# H11R0_Backend.net
KiCad netlist of a schematic drawn in Altium Designer
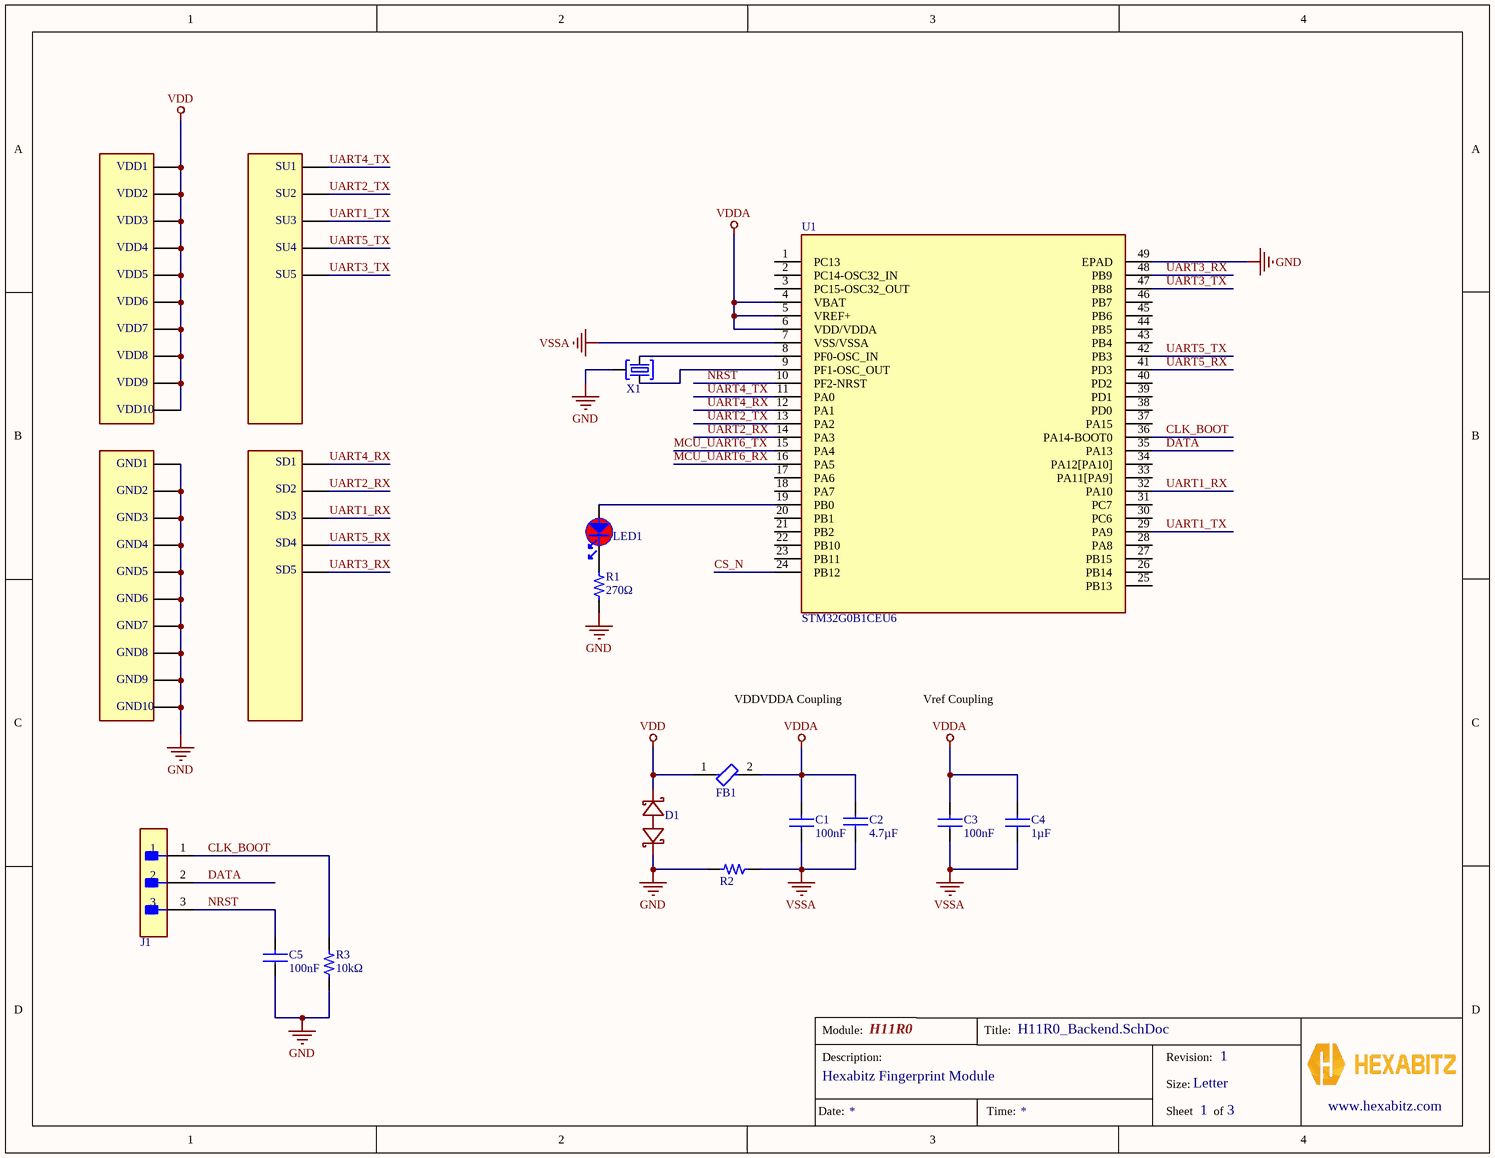
[diagram p0: H11R0_Backend.SchDoc]

(export (version "E")
  (design (tool "Eeschema 10.0.6"))
  (components
    (comp (ref "C1")
      (value "100nF")
      (footprint "C0603")
      (fields
        (field (name "MANUFACTURER") "Samsung Electro-Mechanics")
        (field (name "MANUFACTURER PART NUMBER") "CL10B104KA8NNNC")
        (field (name "TOLERANCE") "10%")
      )
      (libsource (lib "Hexabitz Altium Library") (part "generic Capacitor"))
    )
    (comp (ref "C2")
      (value "4.7µF")
      (footprint "C0805")
      (fields
        (field (name "MANUFACTURER") "Samsung Electro-Mechanics")
        (field (name "MANUFACTURER PART NUMBER") "CL21X475KAQNNNE")
        (field (name "TOLERANCE") "10%")
      )
      (libsource (lib "Hexabitz Altium Library") (part "generic Capacitor"))
    )
    (comp (ref "C3")
      (value "100nF")
      (footprint "C0603")
      (fields
        (field (name "MANUFACTURER") "Samsung Electro-Mechanics")
        (field (name "MANUFACTURER PART NUMBER") "CL10B104KA8NNNC")
        (field (name "TOLERANCE") "10%")
      )
      (libsource (lib "Hexabitz Altium Library") (part "generic Capacitor"))
    )
    (comp (ref "C4")
      (value "1µF")
      (footprint "C0805")
      (description "Ceramic Capacitor, Ceramic, 16V, 10% +Tol, 10% -Tol, X7R, 15% TC, 1uF, Surface Mount, 0805")
      (fields
        (field (name "MANUFACTURER") "Yageo Group")
        (field (name "MANUFACTURER PART NUMBER") "CC0805KKX7R7BB105")
      )
      (libsource (lib "Hexabitz Altium Library") (part "generic Capacitor"))
    )
    (comp (ref "C5")
      (value "100nF")
      (footprint "C0603")
      (fields
        (field (name "MANUFACTURER") "Samsung Electro-Mechanics")
        (field (name "MANUFACTURER PART NUMBER") "CL10B104KA8NNNC")
        (field (name "TOLERANCE") "10%")
      )
      (libsource (lib "Hexabitz Altium Library") (part "generic Capacitor"))
    )
    (comp (ref "D1")
      (value "CDSOD323-T03SC")
      (footprint "SOD2513X114N")
      (description "A 3V, 350W, bi-directional, standard capacitance, SOD323 pkg TVS Diode ¦ Bourns CDSOD323-T03SC")
      (fields (field (name "MANUFACTURER") "Bourns"))
      (libsource (lib "Hexabitz Altium Library") (part "CDSOD323-T03SC"))
    )
    (comp (ref "FB1")
      (value "MMZ1608Y300B")
      (footprint "FP-MMZ1608-0_8-MFG")
      (description "Ferrite Beads 0603 30ohms 1500mA Signal Line AEC-Q200")
      (fields
        (field (name "MANUFACTURER") "TDK")
        (field (name "MANUFACTURER PART NUMBER") "MMZ1608Y300BTD25")
      )
      (libsource (lib "Hexabitz Altium Library") (part "MMZ1608Y300B"))
    )
    (comp (ref "GND1")
      (value "HEXABIT_UART_PORT")
      (footprint "HEXABIT_POWER_PORT_D")
      (libsource (lib "hexabitz_connectors.Library") (part "HEXABIT_POWER_PORT_D"))
    )
    (comp (ref "GND2")
      (value "HEXABIT_UART_PORT")
      (footprint "HEXABIT_POWER_PORT_D")
      (libsource (lib "hexabitz_connectors.Library") (part "HEXABIT_POWER_PORT_D"))
    )
    (comp (ref "GND3")
      (value "HEXABIT_UART_PORT")
      (footprint "HEXABIT_POWER_PORT_D_300R")
      (libsource (lib "hexabitz_connectors.Library") (part "HEXABIT_POWER_PORT_D_300R"))
    )
    (comp (ref "GND4")
      (value "HEXABIT_UART_PORT")
      (footprint "HEXABIT_POWER_PORT_D")
      (libsource (lib "hexabitz_connectors.Library") (part "HEXABIT_POWER_PORT_D"))
    )
    (comp (ref "GND5")
      (value "HEXABIT_UART_PORT")
      (footprint "HEXABIT_POWER_PORT_D")
      (libsource (lib "hexabitz_connectors.Library") (part "HEXABIT_POWER_PORT_D"))
    )
    (comp (ref "GND6")
      (value "HEXABIT_UART_PORT")
      (footprint "HEXABIT_POWER_PORT_D")
      (libsource (lib "hexabitz_connectors.Library") (part "HEXABIT_POWER_PORT_D"))
    )
    (comp (ref "GND7")
      (value "HEXABIT_UART_PORT")
      (footprint "HEXABIT_POWER_PORT_D")
      (libsource (lib "hexabitz_connectors.Library") (part "HEXABIT_POWER_PORT_D"))
    )
    (comp (ref "GND8")
      (value "HEXABIT_UART_PORT")
      (footprint "HEXABIT_POWER_PORT_D_300L")
      (libsource (lib "hexabitz_connectors.Library") (part "HEXABIT_POWER_PORT_D_300L"))
    )
    (comp (ref "GND9")
      (value "HEXABIT_UART_PORT")
      (footprint "HEXABIT_POWER_PORT_D")
      (libsource (lib "hexabitz_connectors.Library") (part "HEXABIT_POWER_PORT_D"))
    )
    (comp (ref "GND10")
      (value "HEXABIT_UART_PORT")
      (footprint "HEXABIT_POWER_PORT_D")
      (libsource (lib "hexabitz_connectors.Library") (part "HEXABIT_POWER_PORT_D"))
    )
    (comp (ref "J1")
      (value "TSW-103-14-G-S")
      (footprint "FP-TSW-103-14-G-S-MFG")
      (description "CONN HEADER VERT 3POS 2.54MM")
      (libsource (lib "Altium Content Vault") (part "cd3439d6ef35ae5d9b27ec4fdd3e828"))
    )
    (comp (ref "LED1")
      (value "VLMS1300-GS08")
      (footprint "FP-6_541-5092_01-4-MFG")
      (description "LED Uni-Color Super Red 639nm 2-Pin Chip 0603(1608Metric) T/R")
      (fields (field (name "MANUFACTURER") "Vishay Semiconductors"))
      (libsource (lib "Hexabitz Altium Library") (part "VLMS1300-GS08"))
    )
    (comp (ref "R1")
      (value "270Ω")
      (footprint "R0603")
      (description "Res Thick Film 0603 270 Ohm 5% 0.1W(1/10W) ±200ppm/C Pad SMD Automotive T/R")
      (fields
        (field (name "MANUFACTURER") "Panasonic")
        (field (name "MANUFACTURER PART NUMBER") "ERJ-3GEYJ271V")
      )
      (libsource (lib "Hexabitz Altium Library") (part "generic Resistor"))
    )
    (comp (ref "R2")
      (value "Manufacturer Part Number")
      (footprint "R0603")
      (libsource (lib "") (part "generic Resistor_1"))
    )
    (comp (ref "R3")
      (value "10kΩ")
      (footprint "R0603")
      (description "100mW Thick Film Resistors ±100ppm/℃ ±1% 10kΩ 0603 Chip Resistor - Surface Mount ROHS")
      (fields
        (field (name "MANUFACTURER") "Yageo Group")
        (field (name "MANUFACTURER PART NUMBER") "RC0603FR-0710KL")
      )
      (libsource (lib "") (part "generic Resistor_2"))
    )
    (comp (ref "SD1")
      (value "HEXABIT_UART_PORT")
      (footprint "HEXABIT_UART_PORT_D")
      (libsource (lib "hexabitz_connectors.Library") (part "HEXABIT_UART_PORT_D"))
    )
    (comp (ref "SD2")
      (value "HEXABIT_UART_PORT")
      (footprint "HEXABIT_UART_PORT_D")
      (libsource (lib "hexabitz_connectors.Library") (part "HEXABIT_UART_PORT_D"))
    )
    (comp (ref "SD3")
      (value "HEXABIT_UART_PORT")
      (footprint "HEXABIT_UART_PORT_D")
      (libsource (lib "hexabitz_connectors.Library") (part "HEXABIT_UART_PORT_D"))
    )
    (comp (ref "SD4")
      (value "HEXABIT_UART_PORT")
      (footprint "HEXABIT_UART_PORT_D")
      (libsource (lib "hexabitz_connectors.Library") (part "HEXABIT_UART_PORT_D"))
    )
    (comp (ref "SD5")
      (value "HEXABIT_UART_PORT")
      (footprint "HEXABIT_UART_PORT_D")
      (libsource (lib "hexabitz_connectors.Library") (part "HEXABIT_UART_PORT_D"))
    )
    (comp (ref "SU1")
      (value "HEXABIT_UART_PORT")
      (footprint "HEXABIT_UART_PORT_U")
      (libsource (lib "hexabitz_connectors.Library") (part "HEXABIT_UART_PORT_U"))
    )
    (comp (ref "SU2")
      (value "HEXABIT_UART_PORT")
      (footprint "HEXABIT_UART_PORT_U")
      (libsource (lib "hexabitz_connectors.Library") (part "HEXABIT_UART_PORT_U"))
    )
    (comp (ref "SU3")
      (value "HEXABIT_UART_PORT")
      (footprint "HEXABIT_UART_PORT_U")
      (libsource (lib "hexabitz_connectors.Library") (part "HEXABIT_UART_PORT_U"))
    )
    (comp (ref "SU4")
      (value "HEXABIT_UART_PORT")
      (footprint "HEXABIT_UART_PORT_U")
      (libsource (lib "hexabitz_connectors.Library") (part "HEXABIT_UART_PORT_U"))
    )
    (comp (ref "SU5")
      (value "HEXABIT_UART_PORT")
      (footprint "HEXABIT_UART_PORT_U")
      (libsource (lib "hexabitz_connectors.Library") (part "HEXABIT_UART_PORT_U"))
    )
    (comp (ref "U1")
      (value "STM32G0B1CEU6")
      (footprint "QFN50P700X700X65-49N-D")
      (description "MCU 32-bit ARM Cortex M0+ RISC 512KB Flash 1.8V/2.5V/3.3V 48-Pin UFQFPN EP Tray")
      (fields
        (field (name "MANUFACTURER") "STMicroelectronics")
        (field (name "MANUFACTURER PART NUMBER") "STM32G0B1CEU6")
      )
      (libsource (lib "Hexabitz Altium Library") (part "STM32G0B1CEU6"))
    )
    (comp (ref "VDD1")
      (value "HEXABIT_UART_PORT")
      (footprint "HEXABIT_POWER_PORT_U")
      (libsource (lib "hexabitz_connectors.Library") (part "HEXABIT_POWER_PORT_U"))
    )
    (comp (ref "VDD2")
      (value "HEXABIT_UART_PORT")
      (footprint "HEXABIT_POWER_PORT_U")
      (libsource (lib "hexabitz_connectors.Library") (part "HEXABIT_POWER_PORT_U"))
    )
    (comp (ref "VDD3")
      (value "HEXABIT_UART_PORT")
      (footprint "HEXABIT_POWER_PORT_U_300R")
      (libsource (lib "hexabitz_connectors.Library") (part "HEXABIT_POWER_PORT_U_300R"))
    )
    (comp (ref "VDD4")
      (value "HEXABIT_UART_PORT")
      (footprint "HEXABIT_POWER_PORT_U")
      (libsource (lib "hexabitz_connectors.Library") (part "HEXABIT_POWER_PORT_U"))
    )
    (comp (ref "VDD5")
      (value "HEXABIT_UART_PORT")
      (footprint "HEXABIT_POWER_PORT_U")
      (libsource (lib "hexabitz_connectors.Library") (part "HEXABIT_POWER_PORT_U"))
    )
    (comp (ref "VDD6")
      (value "HEXABIT_UART_PORT")
      (footprint "HEXABIT_POWER_PORT_U")
      (libsource (lib "hexabitz_connectors.Library") (part "HEXABIT_POWER_PORT_U"))
    )
    (comp (ref "VDD7")
      (value "HEXABIT_UART_PORT")
      (footprint "HEXABIT_POWER_PORT_U")
      (libsource (lib "hexabitz_connectors.Library") (part "HEXABIT_POWER_PORT_U"))
    )
    (comp (ref "VDD8")
      (value "HEXABIT_UART_PORT")
      (footprint "HEXABIT_POWER_PORT_U_300L")
      (libsource (lib "hexabitz_connectors.Library") (part "HEXABIT_POWER_PORT_U_300L"))
    )
    (comp (ref "VDD9")
      (value "HEXABIT_UART_PORT")
      (footprint "HEXABIT_POWER_PORT_U")
      (libsource (lib "hexabitz_connectors.Library") (part "HEXABIT_POWER_PORT_U"))
    )
    (comp (ref "VDD10")
      (value "HEXABIT_UART_PORT")
      (footprint "HEXABIT_POWER_PORT_U")
      (libsource (lib "hexabitz_connectors.Library") (part "HEXABIT_POWER_PORT_U"))
    )
    (comp (ref "X1")
      (value "CSTCE8M00G52Z-R0")
      (footprint "XTALL_CSTCE8M00G52")
      (description "Ceramic Resonator 8MHz ±0.5% (Tol) ±0.2% (Stability) 10pF 40Ohm 3-Pin CSMD T/R")
      (fields (field (name "MANUFACTURER") "Murata") (field (name "TOLERANCE") "0.5%"))
      (libsource (lib "Hexabitz Altium Library") (part "CSTCE8M00G52Z-R0"))
    )
  )
  (nets
    (net (code "1") (name "/CLK_BOOT") (class "Default")
      (node (ref "J1") (pin "1") (pinfunction "1_1") (pintype "passive"))
      (node (ref "R3") (pin "1") (pinfunction "1_1") (pintype "passive"))
      (node (ref "U1") (pin "36") (pinfunction "PA14-BOOT0_36") (pintype "passive"))
    )
    (net (code "2") (name "/CS_N") (class "Default")
      (node (ref "U1") (pin "24") (pinfunction "PB12_24") (pintype "passive"))
    )
    (net (code "3") (name "/DATA") (class "Default")
      (node (ref "J1") (pin "2") (pinfunction "2_2") (pintype "passive"))
      (node (ref "U1") (pin "35") (pinfunction "PA13_35") (pintype "passive"))
    )
    (net (code "4") (name "/MCU_UART6_RX") (class "Default")
      (node (ref "U1") (pin "16") (pinfunction "PA5_16") (pintype "passive"))
    )
    (net (code "5") (name "/MCU_UART6_TX") (class "Default")
      (node (ref "U1") (pin "15") (pinfunction "PA4_15") (pintype "passive"))
    )
    (net (code "6") (name "/NRST") (class "Default")
      (node (ref "C5") (pin "2") (pinfunction "2_2") (pintype "passive"))
      (node (ref "J1") (pin "3") (pinfunction "3_3") (pintype "passive"))
      (node (ref "U1") (pin "10") (pinfunction "PF2-NRST_10") (pintype "passive"))
    )
    (net (code "7") (name "/UART1_RX") (class "Default")
      (node (ref "SD3") (pin "UART_D") (pinfunction "UART_D_UART_D") (pintype "passive"))
      (node (ref "U1") (pin "32") (pinfunction "PA10_32") (pintype "passive"))
    )
    (net (code "8") (name "/UART1_TX") (class "Default")
      (node (ref "SU3") (pin "UART_U") (pinfunction "UART_U_UART_U") (pintype "passive"))
      (node (ref "U1") (pin "29") (pinfunction "PA9_29") (pintype "passive"))
    )
    (net (code "9") (name "/UART2_RX") (class "Default")
      (node (ref "SD2") (pin "UART_D") (pinfunction "UART_D_UART_D") (pintype "passive"))
      (node (ref "U1") (pin "14") (pinfunction "PA3_14") (pintype "passive"))
    )
    (net (code "10") (name "/UART2_TX") (class "Default")
      (node (ref "SU2") (pin "UART_U") (pinfunction "UART_U_UART_U") (pintype "passive"))
      (node (ref "U1") (pin "13") (pinfunction "PA2_13") (pintype "passive"))
    )
    (net (code "11") (name "/UART3_RX") (class "Default")
      (node (ref "SD5") (pin "UART_D") (pinfunction "UART_D_UART_D") (pintype "passive"))
      (node (ref "U1") (pin "48") (pinfunction "PB9_48") (pintype "passive"))
    )
    (net (code "12") (name "/UART3_TX") (class "Default")
      (node (ref "SU5") (pin "UART_U") (pinfunction "UART_U_UART_U") (pintype "passive"))
      (node (ref "U1") (pin "47") (pinfunction "PB8_47") (pintype "passive"))
    )
    (net (code "13") (name "/UART4_RX") (class "Default")
      (node (ref "SD1") (pin "UART_D") (pinfunction "UART_D_UART_D") (pintype "passive"))
      (node (ref "U1") (pin "12") (pinfunction "PA1_12") (pintype "passive"))
    )
    (net (code "14") (name "/UART4_TX") (class "Default")
      (node (ref "SU1") (pin "UART_U") (pinfunction "UART_U_UART_U") (pintype "passive"))
      (node (ref "U1") (pin "11") (pinfunction "PA0_11") (pintype "passive"))
    )
    (net (code "15") (name "/UART5_RX") (class "Default")
      (node (ref "SD4") (pin "UART_D") (pinfunction "UART_D_UART_D") (pintype "passive"))
      (node (ref "U1") (pin "41") (pinfunction "PD3_41") (pintype "passive"))
    )
    (net (code "16") (name "/UART5_TX") (class "Default")
      (node (ref "SU4") (pin "UART_U") (pinfunction "UART_U_UART_U") (pintype "passive"))
      (node (ref "U1") (pin "42") (pinfunction "PB3_42") (pintype "passive"))
    )
    (net (code "17") (name "GND") (class "Default")
      (node (ref "C5") (pin "1") (pinfunction "1_1") (pintype "passive"))
      (node (ref "D1") (pin "1") (pinfunction "A_1") (pintype "passive"))
      (node (ref "GND1") (pin "Pwr_D") (pinfunction "Pwr_D_Pwr_D") (pintype "passive"))
      (node (ref "GND10") (pin "Pwr_D") (pinfunction "Pwr_D_Pwr_D") (pintype "passive"))
      (node (ref "GND2") (pin "Pwr_D") (pinfunction "Pwr_D_Pwr_D") (pintype "passive"))
      (node (ref "GND3") (pin "Pwr_D") (pinfunction "Pwr_D_Pwr_D") (pintype "passive"))
      (node (ref "GND4") (pin "Pwr_D") (pinfunction "Pwr_D_Pwr_D") (pintype "passive"))
      (node (ref "GND5") (pin "Pwr_D") (pinfunction "Pwr_D_Pwr_D") (pintype "passive"))
      (node (ref "GND6") (pin "Pwr_D") (pinfunction "Pwr_D_Pwr_D") (pintype "passive"))
      (node (ref "GND7") (pin "Pwr_D") (pinfunction "Pwr_D_Pwr_D") (pintype "passive"))
      (node (ref "GND8") (pin "Pwr_D") (pinfunction "Pwr_D_Pwr_D") (pintype "passive"))
      (node (ref "GND9") (pin "Pwr_D") (pinfunction "Pwr_D_Pwr_D") (pintype "passive"))
      (node (ref "R1") (pin "1") (pinfunction "1_1") (pintype "passive"))
      (node (ref "R2") (pin "1") (pinfunction "1_1") (pintype "passive"))
      (node (ref "R3") (pin "2") (pinfunction "2_2") (pintype "passive"))
      (node (ref "U1") (pin "49") (pinfunction "EPAD_49") (pintype "passive"))
      (node (ref "X1") (pin "P$2") (pinfunction "2_P$2") (pintype "passive"))
    )
    (net (code "18") (name "Net-(LED1-Pad1)") (class "Default")
      (node (ref "LED1") (pin "1") (pintype "passive"))
      (node (ref "R1") (pin "2") (pinfunction "2_2") (pintype "passive"))
    )
    (net (code "19") (name "Net-(U1-PB0)") (class "Default")
      (node (ref "LED1") (pin "2") (pintype "passive"))
      (node (ref "U1") (pin "19") (pinfunction "PB0_19") (pintype "passive"))
    )
    (net (code "20") (name "Net-(U1-PF0-OSC_IN)") (class "Default")
      (node (ref "U1") (pin "8") (pinfunction "PF0-OSC_IN_8") (pintype "passive"))
      (node (ref "X1") (pin "P$3") (pinfunction "3_P$3") (pintype "passive"))
    )
    (net (code "21") (name "Net-(U1-PF1-OSC_OUT)") (class "Default")
      (node (ref "U1") (pin "9") (pinfunction "PF1-OSC_OUT_9") (pintype "passive"))
      (node (ref "X1") (pin "P$1") (pinfunction "1_P$1") (pintype "passive"))
    )
    (net (code "22") (name "VDD") (class "Default")
      (node (ref "D1") (pin "2") (pinfunction "C_2") (pintype "passive"))
      (node (ref "FB1") (pin "1") (pinfunction "1_1") (pintype "passive"))
      (node (ref "VDD1") (pin "Pwr_U") (pinfunction "Pwr_U_Pwr_U") (pintype "passive"))
      (node (ref "VDD10") (pin "Pwr_U") (pinfunction "Pwr_U_Pwr_U") (pintype "passive"))
      (node (ref "VDD2") (pin "Pwr_U") (pinfunction "Pwr_U_Pwr_U") (pintype "passive"))
      (node (ref "VDD3") (pin "Pwr_U") (pinfunction "Pwr_U_Pwr_U") (pintype "passive"))
      (node (ref "VDD4") (pin "Pwr_U") (pinfunction "Pwr_U_Pwr_U") (pintype "passive"))
      (node (ref "VDD5") (pin "Pwr_U") (pinfunction "Pwr_U_Pwr_U") (pintype "passive"))
      (node (ref "VDD6") (pin "Pwr_U") (pinfunction "Pwr_U_Pwr_U") (pintype "passive"))
      (node (ref "VDD7") (pin "Pwr_U") (pinfunction "Pwr_U_Pwr_U") (pintype "passive"))
      (node (ref "VDD8") (pin "Pwr_U") (pinfunction "Pwr_U_Pwr_U") (pintype "passive"))
      (node (ref "VDD9") (pin "Pwr_U") (pinfunction "Pwr_U_Pwr_U") (pintype "passive"))
    )
    (net (code "23") (name "VDDA") (class "Default")
      (node (ref "C1") (pin "2") (pinfunction "2_2") (pintype "passive"))
      (node (ref "C2") (pin "1") (pinfunction "1_1") (pintype "passive"))
      (node (ref "C3") (pin "2") (pinfunction "2_2") (pintype "passive"))
      (node (ref "C4") (pin "2") (pinfunction "2_2") (pintype "passive"))
      (node (ref "FB1") (pin "2") (pinfunction "2_2") (pintype "passive"))
      (node (ref "U1") (pin "4") (pinfunction "VBAT_4") (pintype "passive"))
      (node (ref "U1") (pin "5") (pinfunction "VREF+_5") (pintype "passive"))
      (node (ref "U1") (pin "6") (pinfunction "VDD/VDDA_6") (pintype "passive"))
    )
    (net (code "24") (name "VSSA") (class "Default")
      (node (ref "C1") (pin "1") (pinfunction "1_1") (pintype "passive"))
      (node (ref "C2") (pin "2") (pinfunction "2_2") (pintype "passive"))
      (node (ref "C3") (pin "1") (pinfunction "1_1") (pintype "passive"))
      (node (ref "C4") (pin "1") (pinfunction "1_1") (pintype "passive"))
      (node (ref "R2") (pin "2") (pinfunction "2_2") (pintype "passive"))
      (node (ref "U1") (pin "7") (pinfunction "VSS/VSSA_7") (pintype "passive"))
    )
    (net (code "25") (name "unconnected-(U1-PA6-Pad17)") (class "Default")
      (node (ref "U1") (pin "17") (pinfunction "PA6_17") (pintype "passive"))
    )
    (net (code "26") (name "unconnected-(U1-PA7-Pad18)") (class "Default")
      (node (ref "U1") (pin "18") (pinfunction "PA7_18") (pintype "passive"))
    )
    (net (code "27") (name "unconnected-(U1-PA8-Pad28)") (class "Default")
      (node (ref "U1") (pin "28") (pinfunction "PA8_28") (pintype "passive"))
    )
    (net (code "28") (name "unconnected-(U1-PA11[PA9]-Pad33)") (class "Default")
      (node (ref "U1") (pin "33") (pinfunction "PA11[PA9]_33") (pintype "passive"))
    )
    (net (code "29") (name "unconnected-(U1-PA12[PA10]-Pad34)") (class "Default")
      (node (ref "U1") (pin "34") (pinfunction "PA12[PA10]_34") (pintype "passive"))
    )
    (net (code "30") (name "unconnected-(U1-PA15-Pad37)") (class "Default")
      (node (ref "U1") (pin "37") (pinfunction "PA15_37") (pintype "passive"))
    )
    (net (code "31") (name "unconnected-(U1-PB1-Pad20)") (class "Default")
      (node (ref "U1") (pin "20") (pinfunction "PB1_20") (pintype "passive"))
    )
    (net (code "32") (name "unconnected-(U1-PB2-Pad21)") (class "Default")
      (node (ref "U1") (pin "21") (pinfunction "PB2_21") (pintype "passive"))
    )
    (net (code "33") (name "unconnected-(U1-PB4-Pad43)") (class "Default")
      (node (ref "U1") (pin "43") (pinfunction "PB4_43") (pintype "passive"))
    )
    (net (code "34") (name "unconnected-(U1-PB5-Pad44)") (class "Default")
      (node (ref "U1") (pin "44") (pinfunction "PB5_44") (pintype "passive"))
    )
    (net (code "35") (name "unconnected-(U1-PB6-Pad45)") (class "Default")
      (node (ref "U1") (pin "45") (pinfunction "PB6_45") (pintype "passive"))
    )
    (net (code "36") (name "unconnected-(U1-PB7-Pad46)") (class "Default")
      (node (ref "U1") (pin "46") (pinfunction "PB7_46") (pintype "passive"))
    )
    (net (code "37") (name "unconnected-(U1-PB10-Pad22)") (class "Default")
      (node (ref "U1") (pin "22") (pinfunction "PB10_22") (pintype "passive"))
    )
    (net (code "38") (name "unconnected-(U1-PB11-Pad23)") (class "Default")
      (node (ref "U1") (pin "23") (pinfunction "PB11_23") (pintype "passive"))
    )
    (net (code "39") (name "unconnected-(U1-PB13-Pad25)") (class "Default")
      (node (ref "U1") (pin "25") (pinfunction "PB13_25") (pintype "passive"))
    )
    (net (code "40") (name "unconnected-(U1-PB14-Pad26)") (class "Default")
      (node (ref "U1") (pin "26") (pinfunction "PB14_26") (pintype "passive"))
    )
    (net (code "41") (name "unconnected-(U1-PB15-Pad27)") (class "Default")
      (node (ref "U1") (pin "27") (pinfunction "PB15_27") (pintype "passive"))
    )
    (net (code "42") (name "unconnected-(U1-PC6-Pad30)") (class "Default")
      (node (ref "U1") (pin "30") (pinfunction "PC6_30") (pintype "passive"))
    )
    (net (code "43") (name "unconnected-(U1-PC7-Pad31)") (class "Default")
      (node (ref "U1") (pin "31") (pinfunction "PC7_31") (pintype "passive"))
    )
    (net (code "44") (name "unconnected-(U1-PC13-Pad1)") (class "Default")
      (node (ref "U1") (pin "1") (pinfunction "PC13_1") (pintype "passive"))
    )
    (net (code "45") (name "unconnected-(U1-PC14-OSC32_IN-Pad2)") (class "Default")
      (node (ref "U1") (pin "2") (pinfunction "PC14-OSC32_IN_2") (pintype "passive"))
    )
    (net (code "46") (name "unconnected-(U1-PC15-OSC32_OUT-Pad3)") (class "Default")
      (node (ref "U1") (pin "3") (pinfunction "PC15-OSC32_OUT_3") (pintype "passive"))
    )
    (net (code "47") (name "unconnected-(U1-PD0-Pad38)") (class "Default")
      (node (ref "U1") (pin "38") (pinfunction "PD0_38") (pintype "passive"))
    )
    (net (code "48") (name "unconnected-(U1-PD1-Pad39)") (class "Default")
      (node (ref "U1") (pin "39") (pinfunction "PD1_39") (pintype "passive"))
    )
    (net (code "49") (name "unconnected-(U1-PD2-Pad40)") (class "Default")
      (node (ref "U1") (pin "40") (pinfunction "PD2_40") (pintype "passive"))
    )
  )
)
